# Transistorverstaerker.net
KiCad netlist of a schematic drawn in Altium Designer
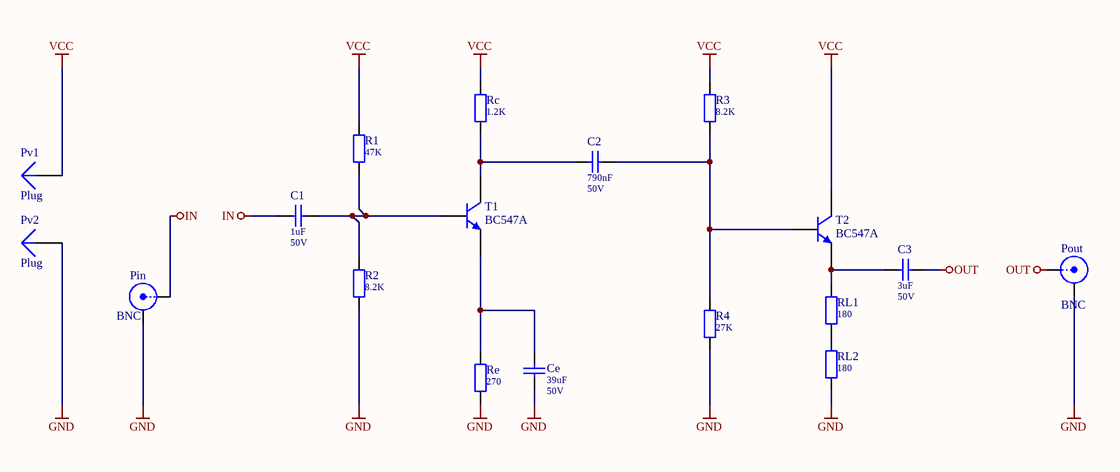
[diagram p0: Transistorverstaerker.SchDoc]

(export (version "E")
  (design (tool "Eeschema 10.0.6"))
  (components
    (comp (ref "C1")
      (value "1uF")
      (footprint "C_RM2-025X075")
      (description "Capacitor")
      (fields (field (name "RATED VOLTAGE") "50V"))
      (libsource (lib "HTLInn_RLCQ") (part "C"))
    )
    (comp (ref "C2")
      (value "790nF")
      (footprint "C_RM2-025X075")
      (description "Capacitor")
      (fields (field (name "RATED VOLTAGE") "50V"))
      (libsource (lib "HTLInn_RLCQ") (part "C"))
    )
    (comp (ref "C3")
      (value "3uF")
      (footprint "C_RM2-025X075")
      (description "Capacitor")
      (fields (field (name "RATED VOLTAGE") "50V"))
      (libsource (lib "HTLInn_RLCQ") (part "C"))
    )
    (comp (ref "Ce")
      (value "39uF")
      (footprint "C_RM2-025X075")
      (description "Capacitor")
      (fields (field (name "RATED VOLTAGE") "50V"))
      (libsource (lib "HTLInn_RLCQ") (part "C"))
    )
    (comp (ref "Pin")
      (value "BNC")
      (footprint "BNC_RA CON")
      (description "BNC Elbow Connector")
      (fields (field (name "PUBLISHER") "Altium Limited"))
      (libsource (lib "Miscellaneous Connectors") (part "BNC"))
    )
    (comp (ref "Pout")
      (value "BNC")
      (footprint "BNC_RA CON")
      (description "BNC Elbow Connector")
      (fields (field (name "PUBLISHER") "Altium Limited"))
      (libsource (lib "Miscellaneous Connectors") (part "BNC"))
    )
    (comp (ref "Pv1")
      (value "Plug")
      (footprint "PIN1")
      (fields (field (name "PUBLISHER") "Altium Limited"))
      (libsource (lib "Miscellaneous Connectors") (part "Plug"))
    )
    (comp (ref "Pv2")
      (value "Plug")
      (footprint "PIN1")
      (fields (field (name "PUBLISHER") "Altium Limited"))
      (libsource (lib "Miscellaneous Connectors") (part "Plug"))
    )
    (comp (ref "R1")
      (value "47K")
      (footprint "R_0207/RM4")
      (description "Resistor")
      (libsource (lib "HTLInn_RLCQ") (part "R"))
    )
    (comp (ref "R2")
      (value "8.2K")
      (footprint "R_0207/RM4")
      (description "Resistor")
      (libsource (lib "HTLInn_RLCQ") (part "R"))
    )
    (comp (ref "R3")
      (value "8.2K")
      (footprint "R_0207/RM4")
      (description "Resistor")
      (libsource (lib "HTLInn_RLCQ") (part "R"))
    )
    (comp (ref "R4")
      (value "27K")
      (footprint "R_0207/RM4")
      (description "Resistor")
      (libsource (lib "HTLInn_RLCQ") (part "R"))
    )
    (comp (ref "Rc")
      (value "1.2K")
      (footprint "R_0207/RM4")
      (description "Resistor")
      (libsource (lib "HTLInn_RLCQ") (part "R"))
    )
    (comp (ref "Re")
      (value "270")
      (footprint "R_0207/RM4")
      (description "Resistor")
      (libsource (lib "HTLInn_RLCQ") (part "R"))
    )
    (comp (ref "RL1")
      (value "180")
      (footprint "R_0207/RM4")
      (description "Resistor")
      (libsource (lib "HTLInn_RLCQ") (part "R"))
    )
    (comp (ref "RL2")
      (value "180")
      (footprint "R_0207/RM4")
      (description "Resistor")
      (libsource (lib "HTLInn_RLCQ") (part "R"))
    )
    (comp (ref "T1")
      (value "BC547A")
      (footprint "TO-92A-2")
      (description "NPN General-purpose Transistor")
      (libsource (lib "HTLinn_BJT") (part "BC547A"))
    )
    (comp (ref "T2")
      (value "BC547A")
      (footprint "TO-92A-2")
      (description "NPN General-purpose Transistor")
      (libsource (lib "HTLinn_BJT") (part "BC547A"))
    )
  )
  (nets
    (net (code "1") (name "GND") (class "Default")
      (node (ref "Ce") (pin "1") (pinfunction "1_1") (pintype "passive"))
      (node (ref "Pin") (pin "2") (pinfunction "Y_2") (pintype "passive"))
      (node (ref "Pout") (pin "2") (pinfunction "Y_2") (pintype "passive"))
      (node (ref "Pv2") (pin "1") (pinfunction "1_1") (pintype "passive"))
      (node (ref "R2") (pin "1") (pinfunction "1_1") (pintype "passive"))
      (node (ref "R4") (pin "1") (pinfunction "1_1") (pintype "passive"))
      (node (ref "RL2") (pin "1") (pinfunction "1_1") (pintype "passive"))
      (node (ref "Re") (pin "1") (pinfunction "1_1") (pintype "passive"))
    )
    (net (code "2") (name "IN") (class "Default")
      (node (ref "C1") (pin "1") (pinfunction "1_1") (pintype "passive"))
      (node (ref "Pin") (pin "1") (pinfunction "X_1") (pintype "passive"))
    )
    (net (code "3") (name "Net-(RL1-Pad1)") (class "Default")
      (node (ref "RL1") (pin "1") (pinfunction "1_1") (pintype "passive"))
      (node (ref "RL2") (pin "2") (pinfunction "2_2") (pintype "passive"))
    )
    (net (code "4") (name "Net-(T1-B)") (class "Default")
      (node (ref "C1") (pin "2") (pinfunction "2_2") (pintype "passive"))
      (node (ref "R1") (pin "1") (pinfunction "1_1") (pintype "passive"))
      (node (ref "R2") (pin "2") (pinfunction "2_2") (pintype "passive"))
      (node (ref "T1") (pin "2") (pinfunction "B_2") (pintype "passive"))
    )
    (net (code "5") (name "Net-(T1-C)") (class "Default")
      (node (ref "C2") (pin "1") (pinfunction "1_1") (pintype "passive"))
      (node (ref "Rc") (pin "1") (pinfunction "1_1") (pintype "passive"))
      (node (ref "T1") (pin "3") (pinfunction "C_3") (pintype "passive"))
    )
    (net (code "6") (name "Net-(T1-E)") (class "Default")
      (node (ref "Ce") (pin "2") (pinfunction "2_2") (pintype "passive"))
      (node (ref "Re") (pin "2") (pinfunction "2_2") (pintype "passive"))
      (node (ref "T1") (pin "1") (pinfunction "E_1") (pintype "passive"))
    )
    (net (code "7") (name "Net-(T2-B)") (class "Default")
      (node (ref "C2") (pin "2") (pinfunction "2_2") (pintype "passive"))
      (node (ref "R3") (pin "1") (pinfunction "1_1") (pintype "passive"))
      (node (ref "R4") (pin "2") (pinfunction "2_2") (pintype "passive"))
      (node (ref "T2") (pin "2") (pinfunction "B_2") (pintype "passive"))
    )
    (net (code "8") (name "Net-(T2-E)") (class "Default")
      (node (ref "C3") (pin "1") (pinfunction "1_1") (pintype "passive"))
      (node (ref "RL1") (pin "2") (pinfunction "2_2") (pintype "passive"))
      (node (ref "T2") (pin "1") (pinfunction "E_1") (pintype "passive"))
    )
    (net (code "9") (name "OUT") (class "Default")
      (node (ref "C3") (pin "2") (pinfunction "2_2") (pintype "passive"))
      (node (ref "Pout") (pin "1") (pinfunction "X_1") (pintype "passive"))
    )
    (net (code "10") (name "VCC") (class "Default")
      (node (ref "Pv1") (pin "1") (pinfunction "1_1") (pintype "passive"))
      (node (ref "R1") (pin "2") (pinfunction "2_2") (pintype "passive"))
      (node (ref "R3") (pin "2") (pinfunction "2_2") (pintype "passive"))
      (node (ref "Rc") (pin "2") (pinfunction "2_2") (pintype "passive"))
      (node (ref "T2") (pin "3") (pinfunction "C_3") (pintype "passive"))
    )
  )
)
